# DAC.net
KiCad netlist of a schematic drawn in Altium Designer
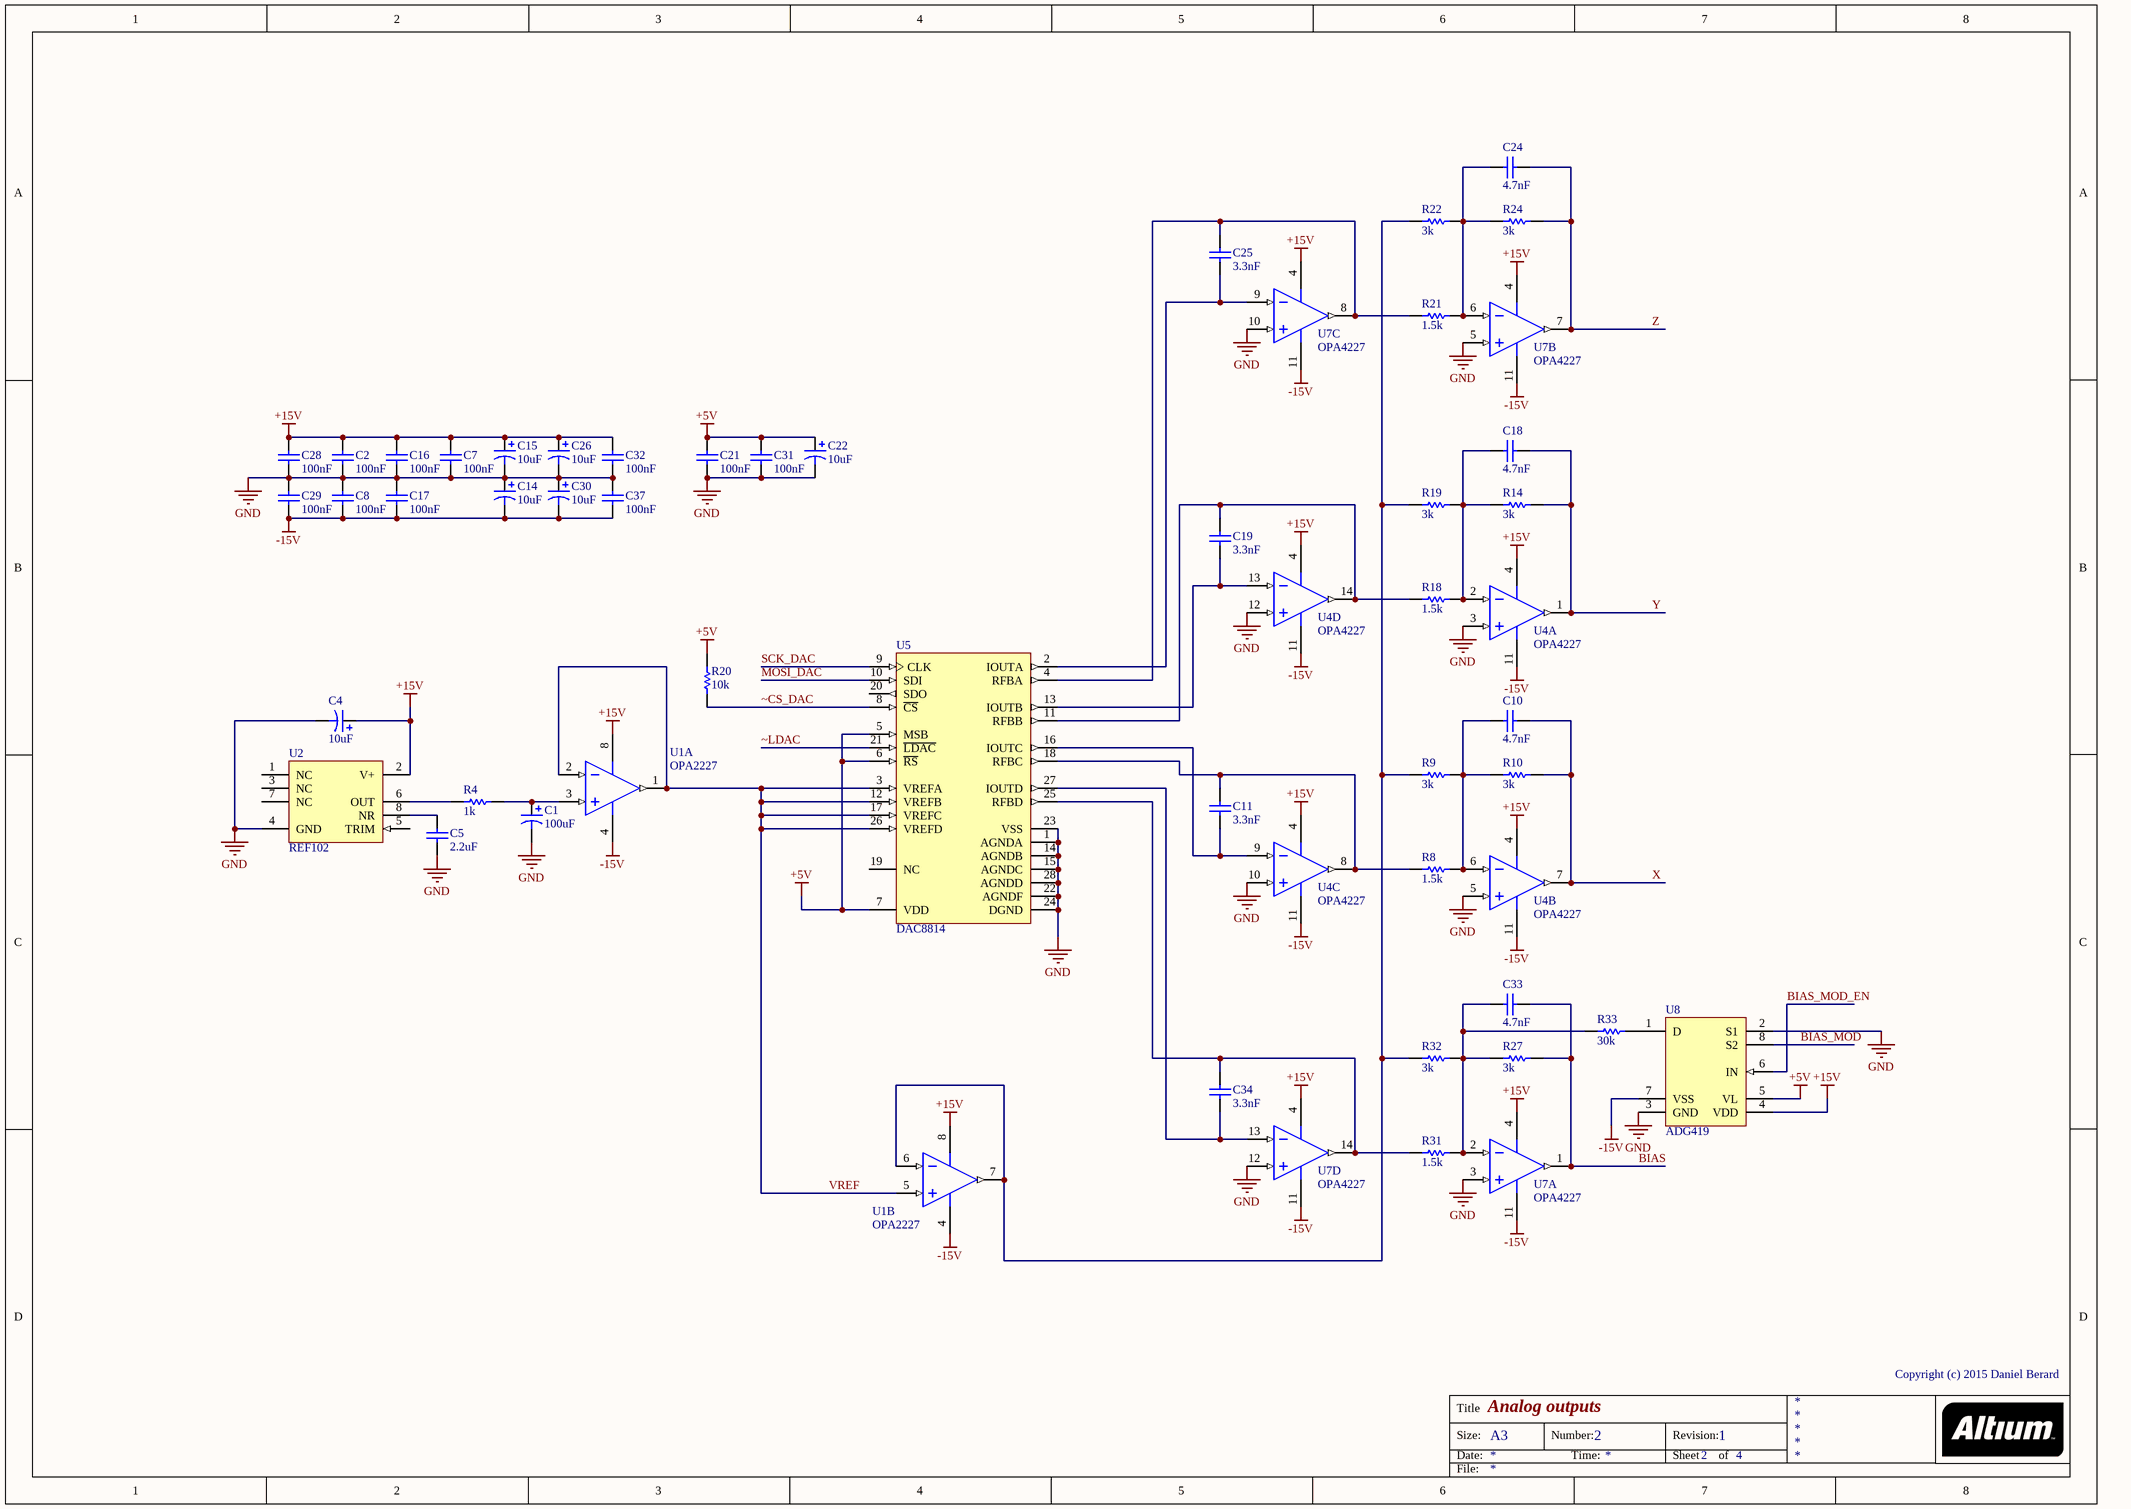
[diagram p0: DAC.SchDoc]

(export (version "E")
  (design (tool "Eeschema 10.0.6"))
  (components
    (comp (ref "C1")
      (value "100uF")
      (footprint "7343")
      (description "Polarized Capacitor (Radial)")
      (fields (field (name "PUBLISHER") "Altium Limited"))
      (libsource (lib "Miscellaneous Devices") (part "Cap Pol1"))
    )
    (comp (ref "C2")
      (value "100nF")
      (footprint "6-0805_N")
      (description "Capacitor")
      (fields (field (name "PUBLISHER") "Altium Limited"))
      (libsource (lib "Miscellaneous Devices") (part "Cap"))
    )
    (comp (ref "C4")
      (value "10uF")
      (footprint "3528")
      (description "Polarized Capacitor (Radial)")
      (fields (field (name "PUBLISHER") "Altium Limited"))
      (libsource (lib "Miscellaneous Devices") (part "Cap Pol1"))
    )
    (comp (ref "C5")
      (value "2.2uF")
      (footprint "C1206")
      (description "Capacitor")
      (fields (field (name "PUBLISHER") "Altium Limited"))
      (libsource (lib "Miscellaneous Devices") (part "Cap"))
    )
    (comp (ref "C7")
      (value "100nF")
      (footprint "6-0805_N")
      (description "Capacitor")
      (fields (field (name "PUBLISHER") "Altium Limited"))
      (libsource (lib "Miscellaneous Devices") (part "Cap"))
    )
    (comp (ref "C8")
      (value "100nF")
      (footprint "6-0805_N")
      (description "Capacitor")
      (fields (field (name "PUBLISHER") "Altium Limited"))
      (libsource (lib "Miscellaneous Devices") (part "Cap"))
    )
    (comp (ref "C10")
      (value "4.7nF")
      (footprint "6-0805_N")
      (description "Capacitor")
      (fields (field (name "PUBLISHER") "Altium Limited"))
      (libsource (lib "Miscellaneous Devices") (part "Cap"))
    )
    (comp (ref "C11")
      (value "3.3nF")
      (footprint "6-0805_N")
      (description "Capacitor")
      (fields (field (name "PUBLISHER") "Altium Limited"))
      (libsource (lib "Miscellaneous Devices") (part "Cap"))
    )
    (comp (ref "C14")
      (value "10uF")
      (footprint "3528")
      (description "Polarized Capacitor (Radial)")
      (fields (field (name "PUBLISHER") "Altium Limited"))
      (libsource (lib "Miscellaneous Devices") (part "Cap Pol1"))
    )
    (comp (ref "C15")
      (value "10uF")
      (footprint "3528")
      (description "Polarized Capacitor (Radial)")
      (fields (field (name "PUBLISHER") "Altium Limited"))
      (libsource (lib "Miscellaneous Devices") (part "Cap Pol1"))
    )
    (comp (ref "C16")
      (value "100nF")
      (footprint "6-0805_N")
      (description "Capacitor")
      (fields (field (name "PUBLISHER") "Altium Limited"))
      (libsource (lib "Miscellaneous Devices") (part "Cap"))
    )
    (comp (ref "C17")
      (value "100nF")
      (footprint "6-0805_N")
      (description "Capacitor")
      (fields (field (name "PUBLISHER") "Altium Limited"))
      (libsource (lib "Miscellaneous Devices") (part "Cap"))
    )
    (comp (ref "C18")
      (value "4.7nF")
      (footprint "6-0805_N")
      (description "Capacitor")
      (fields (field (name "PUBLISHER") "Altium Limited"))
      (libsource (lib "Miscellaneous Devices") (part "Cap"))
    )
    (comp (ref "C19")
      (value "3.3nF")
      (footprint "6-0805_N")
      (description "Capacitor")
      (fields (field (name "PUBLISHER") "Altium Limited"))
      (libsource (lib "Miscellaneous Devices") (part "Cap"))
    )
    (comp (ref "C21")
      (value "100nF")
      (footprint "6-0805_N")
      (description "Capacitor")
      (fields (field (name "PUBLISHER") "Altium Limited"))
      (libsource (lib "Miscellaneous Devices") (part "Cap"))
    )
    (comp (ref "C22")
      (value "10uF")
      (footprint "6-0805_N")
      (description "Polarized Capacitor (Radial)")
      (fields (field (name "PUBLISHER") "Altium Limited"))
      (libsource (lib "Miscellaneous Devices") (part "Cap Pol1"))
    )
    (comp (ref "C24")
      (value "4.7nF")
      (footprint "6-0805_N")
      (description "Capacitor")
      (fields (field (name "PUBLISHER") "Altium Limited"))
      (libsource (lib "Miscellaneous Devices") (part "Cap"))
    )
    (comp (ref "C25")
      (value "3.3nF")
      (footprint "6-0805_N")
      (description "Capacitor")
      (fields (field (name "PUBLISHER") "Altium Limited"))
      (libsource (lib "Miscellaneous Devices") (part "Cap"))
    )
    (comp (ref "C26")
      (value "10uF")
      (footprint "3528")
      (description "Polarized Capacitor (Radial)")
      (fields (field (name "PUBLISHER") "Altium Limited"))
      (libsource (lib "Miscellaneous Devices") (part "Cap Pol1"))
    )
    (comp (ref "C28")
      (value "100nF")
      (footprint "6-0805_N")
      (description "Capacitor")
      (fields (field (name "PUBLISHER") "Altium Limited"))
      (libsource (lib "Miscellaneous Devices") (part "Cap"))
    )
    (comp (ref "C29")
      (value "100nF")
      (footprint "6-0805_N")
      (description "Capacitor")
      (fields (field (name "PUBLISHER") "Altium Limited"))
      (libsource (lib "Miscellaneous Devices") (part "Cap"))
    )
    (comp (ref "C30")
      (value "10uF")
      (footprint "3528")
      (description "Polarized Capacitor (Radial)")
      (fields (field (name "PUBLISHER") "Altium Limited"))
      (libsource (lib "Miscellaneous Devices") (part "Cap Pol1"))
    )
    (comp (ref "C31")
      (value "100nF")
      (footprint "6-0805_N")
      (description "Capacitor")
      (fields (field (name "PUBLISHER") "Altium Limited"))
      (libsource (lib "Miscellaneous Devices") (part "Cap"))
    )
    (comp (ref "C32")
      (value "100nF")
      (footprint "6-0805_N")
      (description "Capacitor")
      (fields (field (name "PUBLISHER") "Altium Limited"))
      (libsource (lib "Miscellaneous Devices") (part "Cap"))
    )
    (comp (ref "C33")
      (value "4.7nF")
      (footprint "6-0805_N")
      (description "Capacitor")
      (fields (field (name "PUBLISHER") "Altium Limited"))
      (libsource (lib "Miscellaneous Devices") (part "Cap"))
    )
    (comp (ref "C34")
      (value "3.3nF")
      (footprint "6-0805_N")
      (description "Capacitor")
      (fields (field (name "PUBLISHER") "Altium Limited"))
      (libsource (lib "Miscellaneous Devices") (part "Cap"))
    )
    (comp (ref "C37")
      (value "100nF")
      (footprint "6-0805_N")
      (description "Capacitor")
      (fields (field (name "PUBLISHER") "Altium Limited"))
      (libsource (lib "Miscellaneous Devices") (part "Cap"))
    )
    (comp (ref "R4")
      (value "1k")
      (footprint "6-0805_N")
      (description "Resistor")
      (fields (field (name "PUBLISHER") "Altium Limited"))
      (libsource (lib "Miscellaneous Devices") (part "Res1"))
    )
    (comp (ref "R8")
      (value "1.5k")
      (footprint "6-0805_N")
      (description "Resistor")
      (fields (field (name "PUBLISHER") "Altium Limited"))
      (libsource (lib "Miscellaneous Devices") (part "Res1"))
    )
    (comp (ref "R9")
      (value "3k")
      (footprint "6-0805_N")
      (description "Resistor")
      (fields (field (name "PUBLISHER") "Altium Limited"))
      (libsource (lib "Miscellaneous Devices") (part "Res1"))
    )
    (comp (ref "R10")
      (value "3k")
      (footprint "6-0805_N")
      (description "Resistor")
      (fields (field (name "PUBLISHER") "Altium Limited"))
      (libsource (lib "Miscellaneous Devices") (part "Res1"))
    )
    (comp (ref "R14")
      (value "3k")
      (footprint "6-0805_N")
      (description "Resistor")
      (fields (field (name "PUBLISHER") "Altium Limited"))
      (libsource (lib "Miscellaneous Devices") (part "Res1"))
    )
    (comp (ref "R18")
      (value "1.5k")
      (footprint "6-0805_N")
      (description "Resistor")
      (fields (field (name "PUBLISHER") "Altium Limited"))
      (libsource (lib "Miscellaneous Devices") (part "Res1"))
    )
    (comp (ref "R19")
      (value "3k")
      (footprint "6-0805_N")
      (description "Resistor")
      (fields (field (name "PUBLISHER") "Altium Limited"))
      (libsource (lib "Miscellaneous Devices") (part "Res1"))
    )
    (comp (ref "R20")
      (value "10k")
      (footprint "6-0805_N")
      (description "Resistor")
      (fields (field (name "PUBLISHER") "Altium Limited"))
      (libsource (lib "Miscellaneous Devices") (part "Res1"))
    )
    (comp (ref "R21")
      (value "1.5k")
      (footprint "6-0805_N")
      (description "Resistor")
      (fields (field (name "PUBLISHER") "Altium Limited"))
      (libsource (lib "Miscellaneous Devices") (part "Res1"))
    )
    (comp (ref "R22")
      (value "3k")
      (footprint "6-0805_N")
      (description "Resistor")
      (fields (field (name "PUBLISHER") "Altium Limited"))
      (libsource (lib "Miscellaneous Devices") (part "Res1"))
    )
    (comp (ref "R24")
      (value "3k")
      (footprint "6-0805_N")
      (description "Resistor")
      (fields (field (name "PUBLISHER") "Altium Limited"))
      (libsource (lib "Miscellaneous Devices") (part "Res1"))
    )
    (comp (ref "R27")
      (value "3k")
      (footprint "6-0805_N")
      (description "Resistor")
      (fields (field (name "PUBLISHER") "Altium Limited"))
      (libsource (lib "Miscellaneous Devices") (part "Res1"))
    )
    (comp (ref "R31")
      (value "1.5k")
      (footprint "6-0805_N")
      (description "Resistor")
      (fields (field (name "PUBLISHER") "Altium Limited"))
      (libsource (lib "Miscellaneous Devices") (part "Res1"))
    )
    (comp (ref "R32")
      (value "3k")
      (footprint "6-0805_N")
      (description "Resistor")
      (fields (field (name "PUBLISHER") "Altium Limited"))
      (libsource (lib "Miscellaneous Devices") (part "Res1"))
    )
    (comp (ref "R33")
      (value "30k")
      (footprint "6-0805_N")
      (description "Resistor")
      (fields (field (name "PUBLISHER") "Altium Limited"))
      (libsource (lib "Miscellaneous Devices") (part "Res1"))
    )
    (comp (ref "U1")
      (value "OPA2227")
      (footprint "ADI-R-8_M")
      (fields
        (field (name "MANUFACTURER") "Analog Devices")
        (field (name "GENERIC PART NUMBER") "AD8676")
        (field (name "PARTNUMBER") "AD8676BRZ")
      )
      (libsource (lib "Altium Content Vault") (part "CMP-0384-01147-2"))
    )
    (comp (ref "U2")
      (value "REF102")
      (footprint "182H_N")
      (description "Precision Voltage Reference")
      (fields (field (name "PUBLISHER") "Altium Limited"))
      (libsource (lib "BB Power Mgt Voltage Reference") (part "REF102AU"))
    )
    (comp (ref "U4")
      (value "OPA4227")
      (footprint "TI-D14_M")
      (fields (field (name "PARTNUMBER") "OPA4227UA/2K5") (field (name "MANUFACTURER") "Texas Instruments"))
      (libsource (lib "Altium Content Vault") (part "CMP-0272-00152-2"))
    )
    (comp (ref "U5")
      (value "DAC8814")
      (footprint "TI-DB28_L")
      (fields (field (name "MANUFACTURER") "Texas Instruments") (field (name "PARTNUMBER") "DAC8814ICDBTG4"))
      (libsource (lib "Altium Content Vault") (part "CMP-0004-00286-1"))
    )
    (comp (ref "U7")
      (value "OPA4227")
      (footprint "TI-D14_M")
      (fields (field (name "PARTNUMBER") "OPA4227UA/2K5") (field (name "MANUFACTURER") "Texas Instruments"))
      (libsource (lib "Altium Content Vault") (part "CMP-0272-00152-2"))
    )
    (comp (ref "U8")
      (value "ADG419")
      (footprint "ADI-RM-8_N")
      (description "LC2MOS Precision Mini-DIP Analog Switches, 25 Ohm Ron, 8-pin SOP (RM-8), Tube")
      (fields (field (name "MANUFACTURER") "Analog Devices") (field (name "PARTNUMBER") "ADG419BRMZ"))
      (libsource (lib "Altium Content Vault") (part "CMP-0792-00196-1"))
    )
  )
  (nets
    (net (code "1") (name "+5V") (class "Default")
      (node (ref "C21") (pin "2") (pinfunction "2_2") (pintype "passive"))
      (node (ref "C22") (pin "1") (pinfunction "1_1") (pintype "passive"))
      (node (ref "C31") (pin "2") (pinfunction "2_2") (pintype "passive"))
      (node (ref "R20") (pin "2") (pinfunction "2_2") (pintype "passive"))
      (node (ref "U5") (pin "5") (pinfunction "MSB_5") (pintype "input"))
      (node (ref "U5") (pin "6") (pinfunction "~{RS}_6") (pintype "input"))
      (node (ref "U5") (pin "7") (pinfunction "VDD_7") (pintype "power_in"))
      (node (ref "U8") (pin "5") (pinfunction "VL_5") (pintype "power_in"))
    )
    (net (code "2") (name "+15V") (class "Default")
      (node (ref "C15") (pin "1") (pinfunction "1_1") (pintype "passive"))
      (node (ref "C16") (pin "2") (pinfunction "2_2") (pintype "passive"))
      (node (ref "C2") (pin "2") (pinfunction "2_2") (pintype "passive"))
      (node (ref "C26") (pin "1") (pinfunction "1_1") (pintype "passive"))
      (node (ref "C28") (pin "2") (pinfunction "2_2") (pintype "passive"))
      (node (ref "C32") (pin "2") (pinfunction "2_2") (pintype "passive"))
      (node (ref "C4") (pin "1") (pinfunction "1_1") (pintype "passive"))
      (node (ref "C7") (pin "1") (pinfunction "1_1") (pintype "passive"))
      (node (ref "U1") (pin "8") (pinfunction "+V_8") (pintype "power_in"))
      (node (ref "U2") (pin "2") (pinfunction "V+_2") (pintype "power_in"))
      (node (ref "U4") (pin "4") (pinfunction "V+_4") (pintype "power_in"))
      (node (ref "U7") (pin "4") (pinfunction "V+_4") (pintype "power_in"))
      (node (ref "U8") (pin "4") (pinfunction "VDD_4") (pintype "power_in"))
    )
    (net (code "3") (name "-15V") (class "Default")
      (node (ref "C14") (pin "2") (pinfunction "2_2") (pintype "passive"))
      (node (ref "C17") (pin "1") (pinfunction "1_1") (pintype "passive"))
      (node (ref "C29") (pin "1") (pinfunction "1_1") (pintype "passive"))
      (node (ref "C30") (pin "2") (pinfunction "2_2") (pintype "passive"))
      (node (ref "C37") (pin "1") (pinfunction "1_1") (pintype "passive"))
      (node (ref "C8") (pin "1") (pinfunction "1_1") (pintype "passive"))
      (node (ref "U1") (pin "4") (pinfunction "-V_4") (pintype "power_in"))
      (node (ref "U4") (pin "11") (pinfunction "V-_11") (pintype "power_in"))
      (node (ref "U7") (pin "11") (pinfunction "V-_11") (pintype "power_in"))
      (node (ref "U8") (pin "7") (pinfunction "VSS_7") (pintype "power_in"))
    )
    (net (code "4") (name "/BIAS") (class "Default")
      (node (ref "C33") (pin "2") (pinfunction "2_2") (pintype "passive"))
      (node (ref "R27") (pin "2") (pinfunction "2_2") (pintype "passive"))
      (node (ref "U7") (pin "1") (pinfunction "OUT_A_1") (pintype "output"))
    )
    (net (code "5") (name "/BIAS_MOD") (class "Default")
      (node (ref "U8") (pin "8") (pinfunction "S2_8") (pintype "passive"))
    )
    (net (code "6") (name "/BIAS_MOD_EN") (class "Default")
      (node (ref "U8") (pin "6") (pinfunction "IN_6") (pintype "input"))
    )
    (net (code "7") (name "/MOSI_DAC") (class "Default")
      (node (ref "U5") (pin "10") (pinfunction "SDI_10") (pintype "input"))
    )
    (net (code "8") (name "/SCK_DAC") (class "Default")
      (node (ref "U5") (pin "9") (pinfunction "CLK_9") (pintype "input"))
    )
    (net (code "9") (name "/VREF") (class "Default")
      (node (ref "U1") (pin "1") (pinfunction "OUT_A_1") (pintype "output"))
      (node (ref "U1") (pin "2") (pinfunction "-IN_A_2") (pintype "input"))
      (node (ref "U1") (pin "5") (pinfunction "+IN_B_5") (pintype "input"))
      (node (ref "U5") (pin "12") (pinfunction "VREFB_12") (pintype "input"))
      (node (ref "U5") (pin "17") (pinfunction "VREFC_17") (pintype "input"))
      (node (ref "U5") (pin "26") (pinfunction "VREFD_26") (pintype "input"))
      (node (ref "U5") (pin "3") (pinfunction "VREFA_3") (pintype "input"))
    )
    (net (code "10") (name "/X") (class "Default")
      (node (ref "C10") (pin "2") (pinfunction "2_2") (pintype "passive"))
      (node (ref "R10") (pin "2") (pinfunction "2_2") (pintype "passive"))
      (node (ref "U4") (pin "7") (pinfunction "OUT_B_7") (pintype "output"))
    )
    (net (code "11") (name "/Y") (class "Default")
      (node (ref "C18") (pin "2") (pinfunction "2_2") (pintype "passive"))
      (node (ref "R14") (pin "2") (pinfunction "2_2") (pintype "passive"))
      (node (ref "U4") (pin "1") (pinfunction "OUT_A_1") (pintype "output"))
    )
    (net (code "12") (name "/Z") (class "Default")
      (node (ref "C24") (pin "2") (pinfunction "2_2") (pintype "passive"))
      (node (ref "R24") (pin "2") (pinfunction "2_2") (pintype "passive"))
      (node (ref "U7") (pin "7") (pinfunction "OUT_B_7") (pintype "output"))
    )
    (net (code "13") (name "/~CS_DAC") (class "Default")
      (node (ref "R20") (pin "1") (pinfunction "1_1") (pintype "passive"))
      (node (ref "U5") (pin "8") (pinfunction "~{CS}_8") (pintype "input"))
    )
    (net (code "14") (name "/~LDAC") (class "Default")
      (node (ref "U5") (pin "21") (pinfunction "~{LDAC}_21") (pintype "input"))
    )
    (net (code "15") (name "GND") (class "Default")
      (node (ref "C1") (pin "2") (pinfunction "2_2") (pintype "passive"))
      (node (ref "C14") (pin "1") (pinfunction "1_1") (pintype "passive"))
      (node (ref "C15") (pin "2") (pinfunction "2_2") (pintype "passive"))
      (node (ref "C16") (pin "1") (pinfunction "1_1") (pintype "passive"))
      (node (ref "C17") (pin "2") (pinfunction "2_2") (pintype "passive"))
      (node (ref "C2") (pin "1") (pinfunction "1_1") (pintype "passive"))
      (node (ref "C21") (pin "1") (pinfunction "1_1") (pintype "passive"))
      (node (ref "C22") (pin "2") (pinfunction "2_2") (pintype "passive"))
      (node (ref "C26") (pin "2") (pinfunction "2_2") (pintype "passive"))
      (node (ref "C28") (pin "1") (pinfunction "1_1") (pintype "passive"))
      (node (ref "C29") (pin "2") (pinfunction "2_2") (pintype "passive"))
      (node (ref "C30") (pin "1") (pinfunction "1_1") (pintype "passive"))
      (node (ref "C31") (pin "1") (pinfunction "1_1") (pintype "passive"))
      (node (ref "C32") (pin "1") (pinfunction "1_1") (pintype "passive"))
      (node (ref "C37") (pin "2") (pinfunction "2_2") (pintype "passive"))
      (node (ref "C4") (pin "2") (pinfunction "2_2") (pintype "passive"))
      (node (ref "C5") (pin "2") (pinfunction "2_2") (pintype "passive"))
      (node (ref "C7") (pin "2") (pinfunction "2_2") (pintype "passive"))
      (node (ref "C8") (pin "2") (pinfunction "2_2") (pintype "passive"))
      (node (ref "U2") (pin "4") (pinfunction "GND_4") (pintype "power_in"))
      (node (ref "U4") (pin "10") (pinfunction "IN_C+_10") (pintype "input"))
      (node (ref "U4") (pin "12") (pinfunction "IN_D+_12") (pintype "input"))
      (node (ref "U4") (pin "3") (pinfunction "IN_A+_3") (pintype "input"))
      (node (ref "U4") (pin "5") (pinfunction "IN_B+_5") (pintype "input"))
      (node (ref "U5") (pin "1") (pinfunction "AGNDA_1") (pintype "power_in"))
      (node (ref "U5") (pin "14") (pinfunction "AGNDB_14") (pintype "power_in"))
      (node (ref "U5") (pin "15") (pinfunction "AGNDC_15") (pintype "power_in"))
      (node (ref "U5") (pin "22") (pinfunction "AGNDF_22") (pintype "power_in"))
      (node (ref "U5") (pin "23") (pinfunction "VSS_23") (pintype "passive"))
      (node (ref "U5") (pin "24") (pinfunction "DGND_24") (pintype "power_in"))
      (node (ref "U5") (pin "28") (pinfunction "AGNDD_28") (pintype "power_in"))
      (node (ref "U7") (pin "10") (pinfunction "IN_C+_10") (pintype "input"))
      (node (ref "U7") (pin "12") (pinfunction "IN_D+_12") (pintype "input"))
      (node (ref "U7") (pin "3") (pinfunction "IN_A+_3") (pintype "input"))
      (node (ref "U7") (pin "5") (pinfunction "IN_B+_5") (pintype "input"))
      (node (ref "U8") (pin "2") (pinfunction "S1_2") (pintype "passive"))
      (node (ref "U8") (pin "3") (pinfunction "GND_3") (pintype "power_in"))
    )
    (net (code "16") (name "Net-(U1A-+IN_A)") (class "Default")
      (node (ref "C1") (pin "1") (pinfunction "1_1") (pintype "passive"))
      (node (ref "R4") (pin "2") (pinfunction "2_2") (pintype "passive"))
      (node (ref "U1") (pin "3") (pinfunction "+IN_A_3") (pintype "input"))
    )
    (net (code "17") (name "Net-(U1B--IN_B)") (class "Default")
      (node (ref "R19") (pin "1") (pinfunction "1_1") (pintype "passive"))
      (node (ref "R22") (pin "1") (pinfunction "1_1") (pintype "passive"))
      (node (ref "R32") (pin "1") (pinfunction "1_1") (pintype "passive"))
      (node (ref "R9") (pin "1") (pinfunction "1_1") (pintype "passive"))
      (node (ref "U1") (pin "6") (pinfunction "-IN_B_6") (pintype "input"))
      (node (ref "U1") (pin "7") (pinfunction "OUT_B_7") (pintype "output"))
    )
    (net (code "18") (name "Net-(U2-NR)") (class "Default")
      (node (ref "C5") (pin "1") (pinfunction "1_1") (pintype "passive"))
      (node (ref "U2") (pin "8") (pinfunction "NR_8") (pintype "passive"))
    )
    (net (code "19") (name "Net-(U2-OUT)") (class "Default")
      (node (ref "R4") (pin "1") (pinfunction "1_1") (pintype "passive"))
      (node (ref "U2") (pin "6") (pinfunction "OUT_6") (pintype "power_in"))
    )
    (net (code "20") (name "Net-(U4A-IN_A-)") (class "Default")
      (node (ref "C18") (pin "1") (pinfunction "1_1") (pintype "passive"))
      (node (ref "R14") (pin "1") (pinfunction "1_1") (pintype "passive"))
      (node (ref "R18") (pin "2") (pinfunction "2_2") (pintype "passive"))
      (node (ref "R19") (pin "2") (pinfunction "2_2") (pintype "passive"))
      (node (ref "U4") (pin "2") (pinfunction "IN_A-_2") (pintype "input"))
    )
    (net (code "21") (name "Net-(U4B-IN_B-)") (class "Default")
      (node (ref "C10") (pin "1") (pinfunction "1_1") (pintype "passive"))
      (node (ref "R10") (pin "1") (pinfunction "1_1") (pintype "passive"))
      (node (ref "R8") (pin "2") (pinfunction "2_2") (pintype "passive"))
      (node (ref "R9") (pin "2") (pinfunction "2_2") (pintype "passive"))
      (node (ref "U4") (pin "6") (pinfunction "IN_B-_6") (pintype "input"))
    )
    (net (code "22") (name "Net-(U4C-IN_C-)") (class "Default")
      (node (ref "C11") (pin "1") (pinfunction "1_1") (pintype "passive"))
      (node (ref "U4") (pin "9") (pinfunction "IN_C-_9") (pintype "input"))
      (node (ref "U5") (pin "16") (pinfunction "IOUTC_16") (pintype "output"))
    )
    (net (code "23") (name "Net-(U4C-OUT_C)") (class "Default")
      (node (ref "C11") (pin "2") (pinfunction "2_2") (pintype "passive"))
      (node (ref "R8") (pin "1") (pinfunction "1_1") (pintype "passive"))
      (node (ref "U4") (pin "8") (pinfunction "OUT_C_8") (pintype "output"))
      (node (ref "U5") (pin "18") (pinfunction "RFBC_18") (pintype "output"))
    )
    (net (code "24") (name "Net-(U4D-IN_D-)") (class "Default")
      (node (ref "C19") (pin "1") (pinfunction "1_1") (pintype "passive"))
      (node (ref "U4") (pin "13") (pinfunction "IN_D-_13") (pintype "input"))
      (node (ref "U5") (pin "13") (pinfunction "IOUTB_13") (pintype "output"))
    )
    (net (code "25") (name "Net-(U4D-OUT_D)") (class "Default")
      (node (ref "C19") (pin "2") (pinfunction "2_2") (pintype "passive"))
      (node (ref "R18") (pin "1") (pinfunction "1_1") (pintype "passive"))
      (node (ref "U4") (pin "14") (pinfunction "OUT_D_14") (pintype "output"))
      (node (ref "U5") (pin "11") (pinfunction "RFBB_11") (pintype "output"))
    )
    (net (code "26") (name "Net-(U5-IOUTA)") (class "Default")
      (node (ref "C25") (pin "1") (pinfunction "1_1") (pintype "passive"))
      (node (ref "U5") (pin "2") (pinfunction "IOUTA_2") (pintype "output"))
      (node (ref "U7") (pin "9") (pinfunction "IN_C-_9") (pintype "input"))
    )
    (net (code "27") (name "Net-(U5-IOUTD)") (class "Default")
      (node (ref "C34") (pin "1") (pinfunction "1_1") (pintype "passive"))
      (node (ref "U5") (pin "27") (pinfunction "IOUTD_27") (pintype "output"))
      (node (ref "U7") (pin "13") (pinfunction "IN_D-_13") (pintype "input"))
    )
    (net (code "28") (name "Net-(U5-RFBA)") (class "Default")
      (node (ref "C25") (pin "2") (pinfunction "2_2") (pintype "passive"))
      (node (ref "R21") (pin "1") (pinfunction "1_1") (pintype "passive"))
      (node (ref "U5") (pin "4") (pinfunction "RFBA_4") (pintype "output"))
      (node (ref "U7") (pin "8") (pinfunction "OUT_C_8") (pintype "output"))
    )
    (net (code "29") (name "Net-(U5-RFBD)") (class "Default")
      (node (ref "C34") (pin "2") (pinfunction "2_2") (pintype "passive"))
      (node (ref "R31") (pin "1") (pinfunction "1_1") (pintype "passive"))
      (node (ref "U5") (pin "25") (pinfunction "RFBD_25") (pintype "output"))
      (node (ref "U7") (pin "14") (pinfunction "OUT_D_14") (pintype "output"))
    )
    (net (code "30") (name "Net-(U7A-IN_A-)") (class "Default")
      (node (ref "C33") (pin "1") (pinfunction "1_1") (pintype "passive"))
      (node (ref "R27") (pin "1") (pinfunction "1_1") (pintype "passive"))
      (node (ref "R31") (pin "2") (pinfunction "2_2") (pintype "passive"))
      (node (ref "R32") (pin "2") (pinfunction "2_2") (pintype "passive"))
      (node (ref "R33") (pin "1") (pinfunction "1_1") (pintype "passive"))
      (node (ref "U7") (pin "2") (pinfunction "IN_A-_2") (pintype "input"))
    )
    (net (code "31") (name "Net-(U7B-IN_B-)") (class "Default")
      (node (ref "C24") (pin "1") (pinfunction "1_1") (pintype "passive"))
      (node (ref "R21") (pin "2") (pinfunction "2_2") (pintype "passive"))
      (node (ref "R22") (pin "2") (pinfunction "2_2") (pintype "passive"))
      (node (ref "R24") (pin "1") (pinfunction "1_1") (pintype "passive"))
      (node (ref "U7") (pin "6") (pinfunction "IN_B-_6") (pintype "input"))
    )
    (net (code "32") (name "Net-(U8-D)") (class "Default")
      (node (ref "R33") (pin "2") (pinfunction "2_2") (pintype "passive"))
      (node (ref "U8") (pin "1") (pinfunction "D_1") (pintype "passive"))
    )
    (net (code "33") (name "unconnected-(U2-NC-Pad1)") (class "Default")
      (node (ref "U2") (pin "1") (pinfunction "NC_1") (pintype "passive"))
    )
    (net (code "34") (name "unconnected-(U2-NC-Pad3)") (class "Default")
      (node (ref "U2") (pin "3") (pinfunction "NC_3") (pintype "passive"))
    )
    (net (code "35") (name "unconnected-(U2-NC-Pad7)") (class "Default")
      (node (ref "U2") (pin "7") (pinfunction "NC_7") (pintype "passive"))
    )
    (net (code "36") (name "unconnected-(U2-TRIM-Pad5)") (class "Default")
      (node (ref "U2") (pin "5") (pinfunction "TRIM_5") (pintype "input"))
    )
    (net (code "37") (name "unconnected-(U5-NC-Pad19)") (class "Default")
      (node (ref "U5") (pin "19") (pinfunction "NC_19") (pintype "passive"))
    )
    (net (code "38") (name "unconnected-(U5-SDO-Pad20)") (class "Default")
      (node (ref "U5") (pin "20") (pinfunction "SDO_20") (pintype "output"))
    )
  )
)
